# cnc_1_0_0.net
KiCad netlist of a schematic drawn in EAGLE
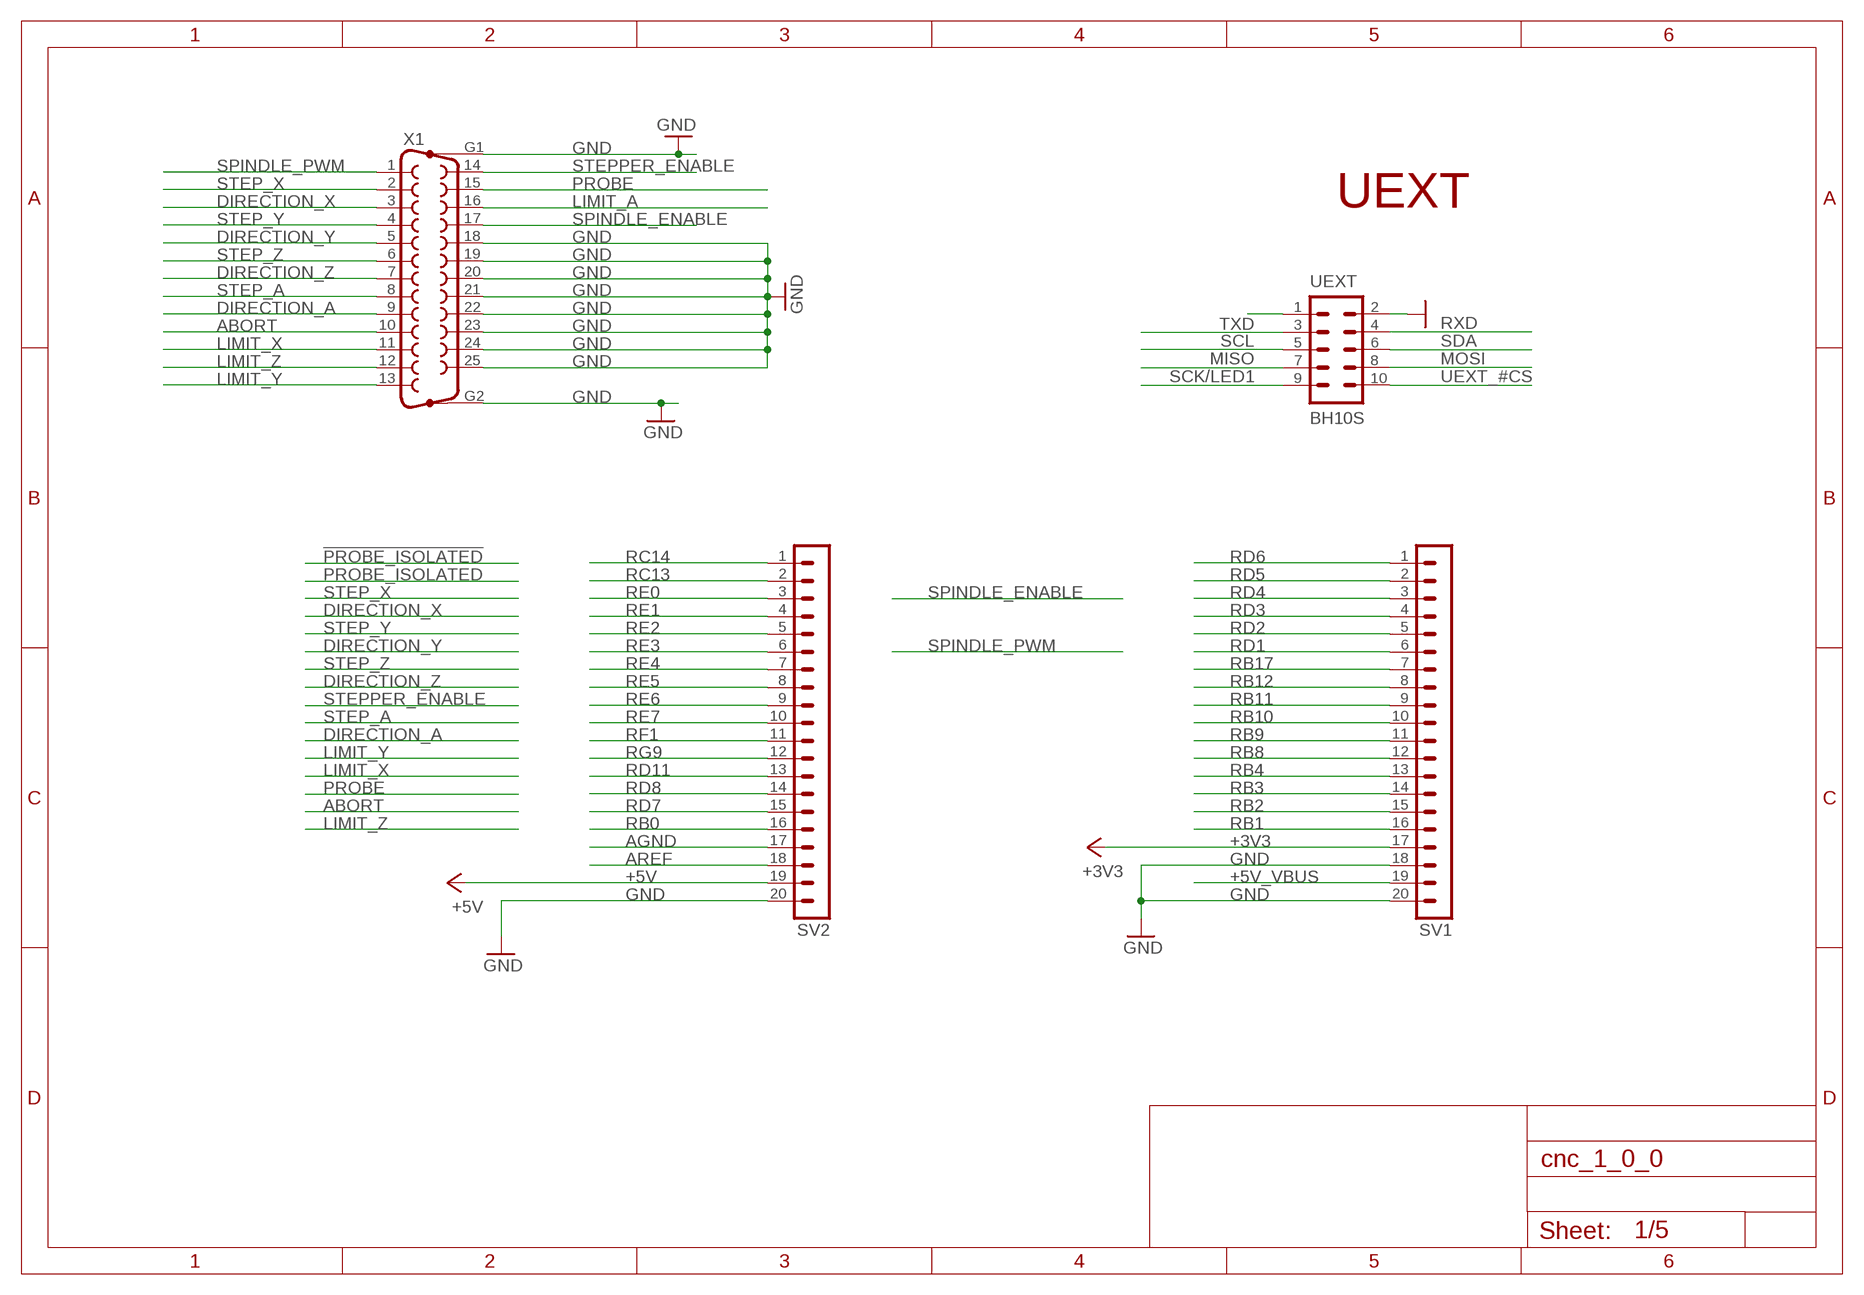
[diagram p0: schematic, sheet 1]
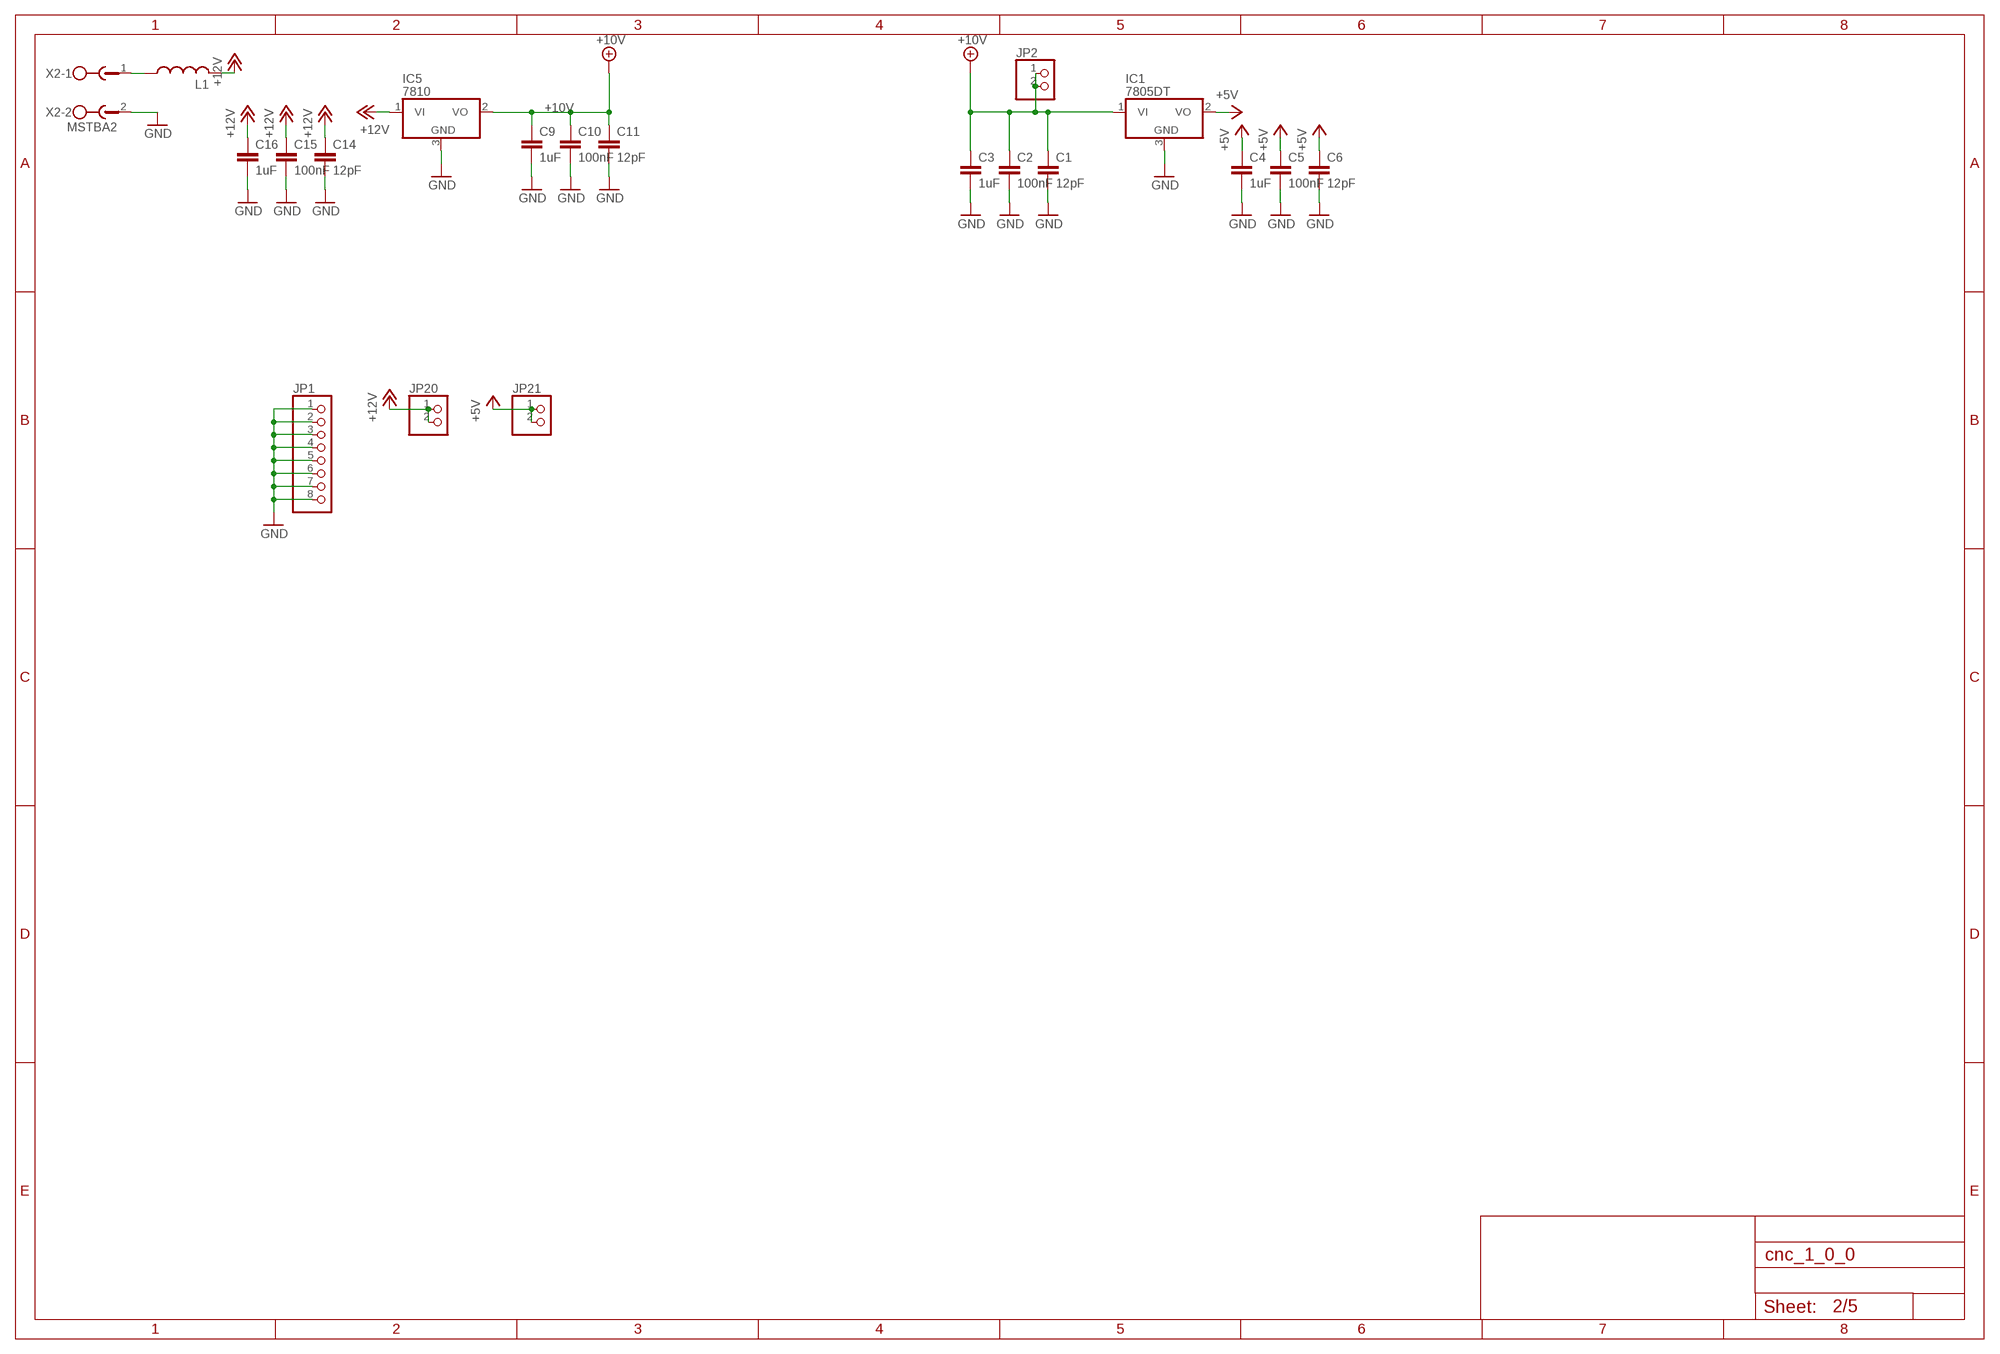
[diagram p1: schematic, sheet 2]
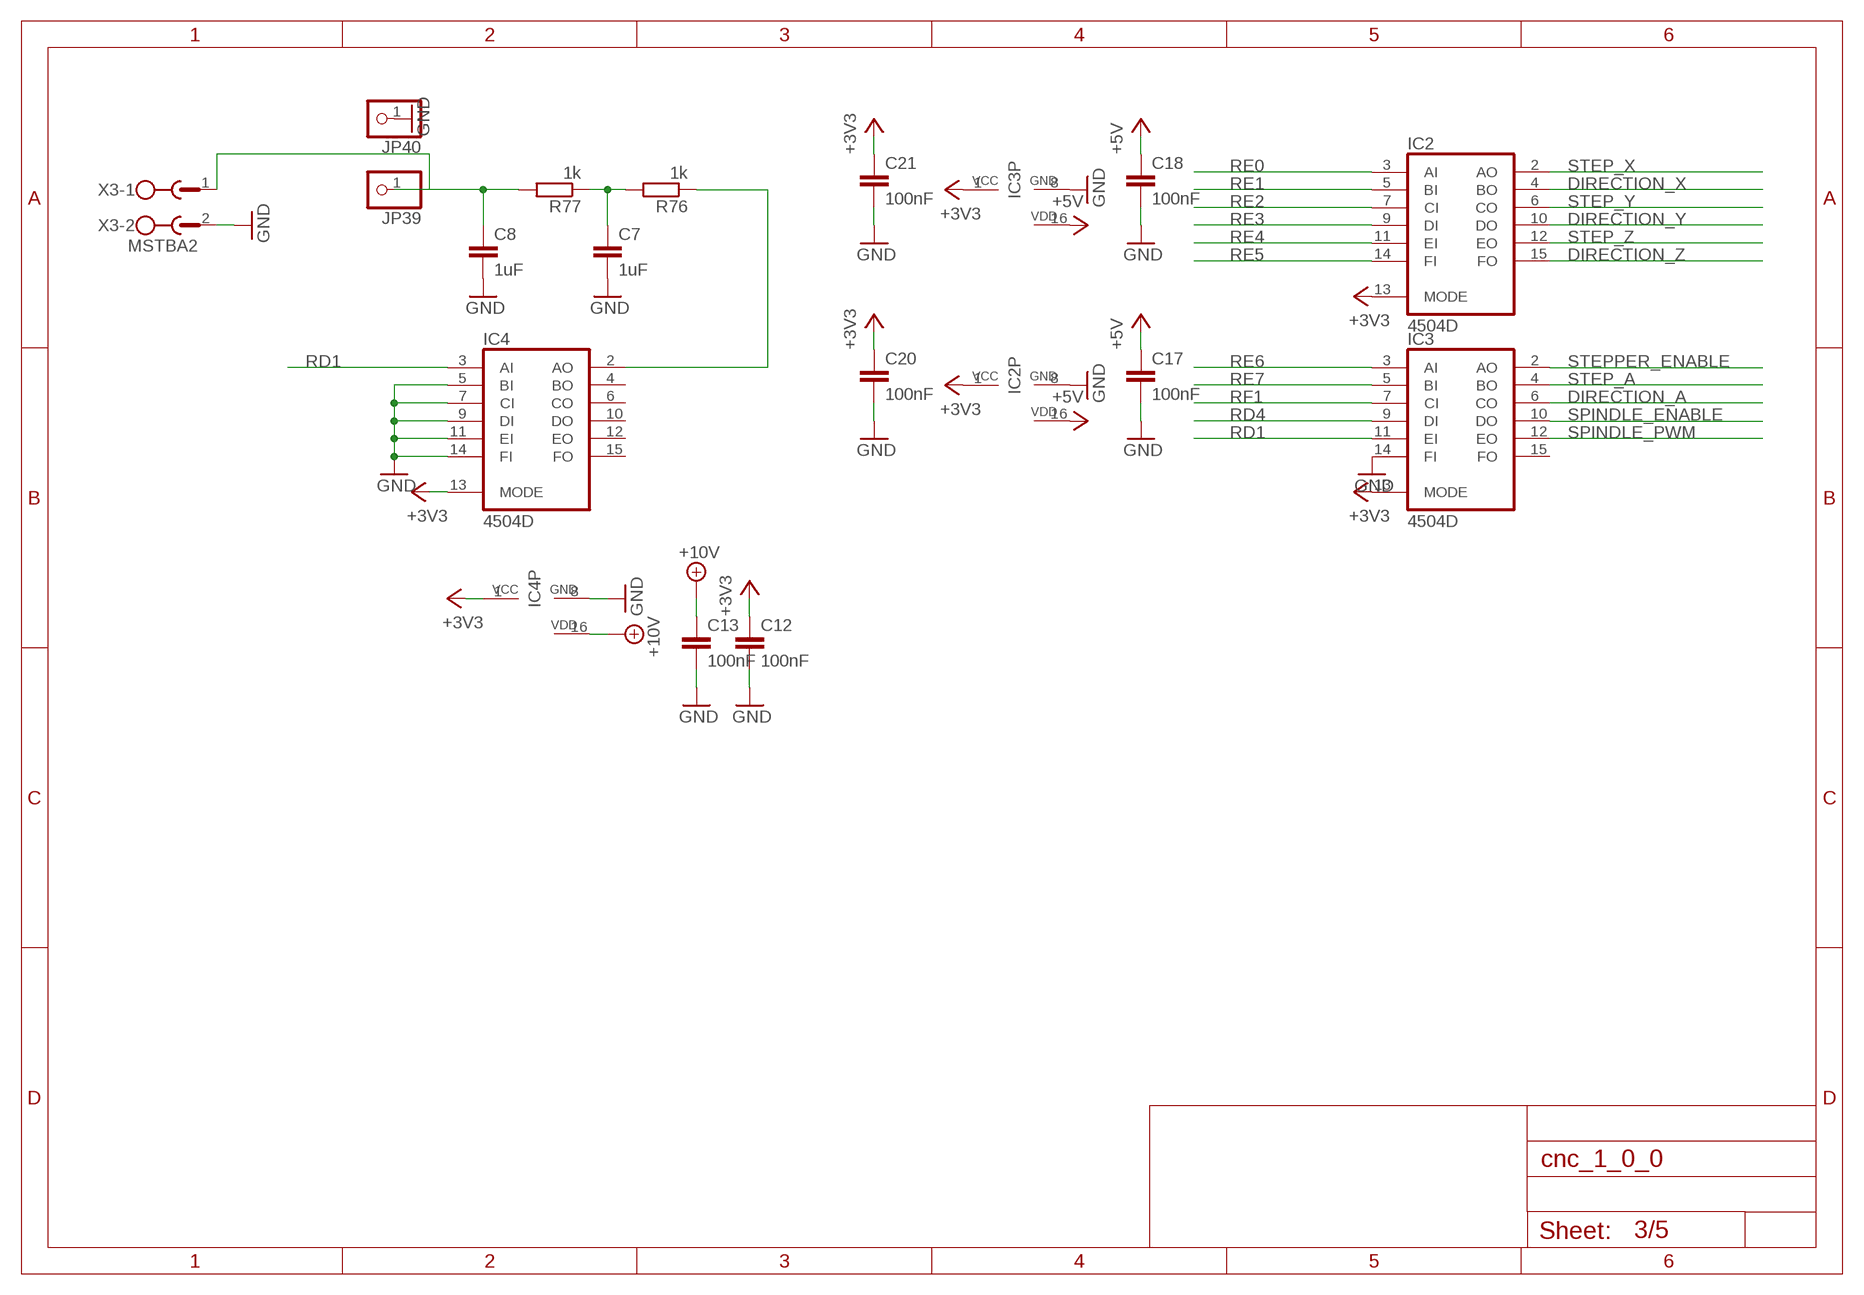
[diagram p2: schematic, sheet 3]
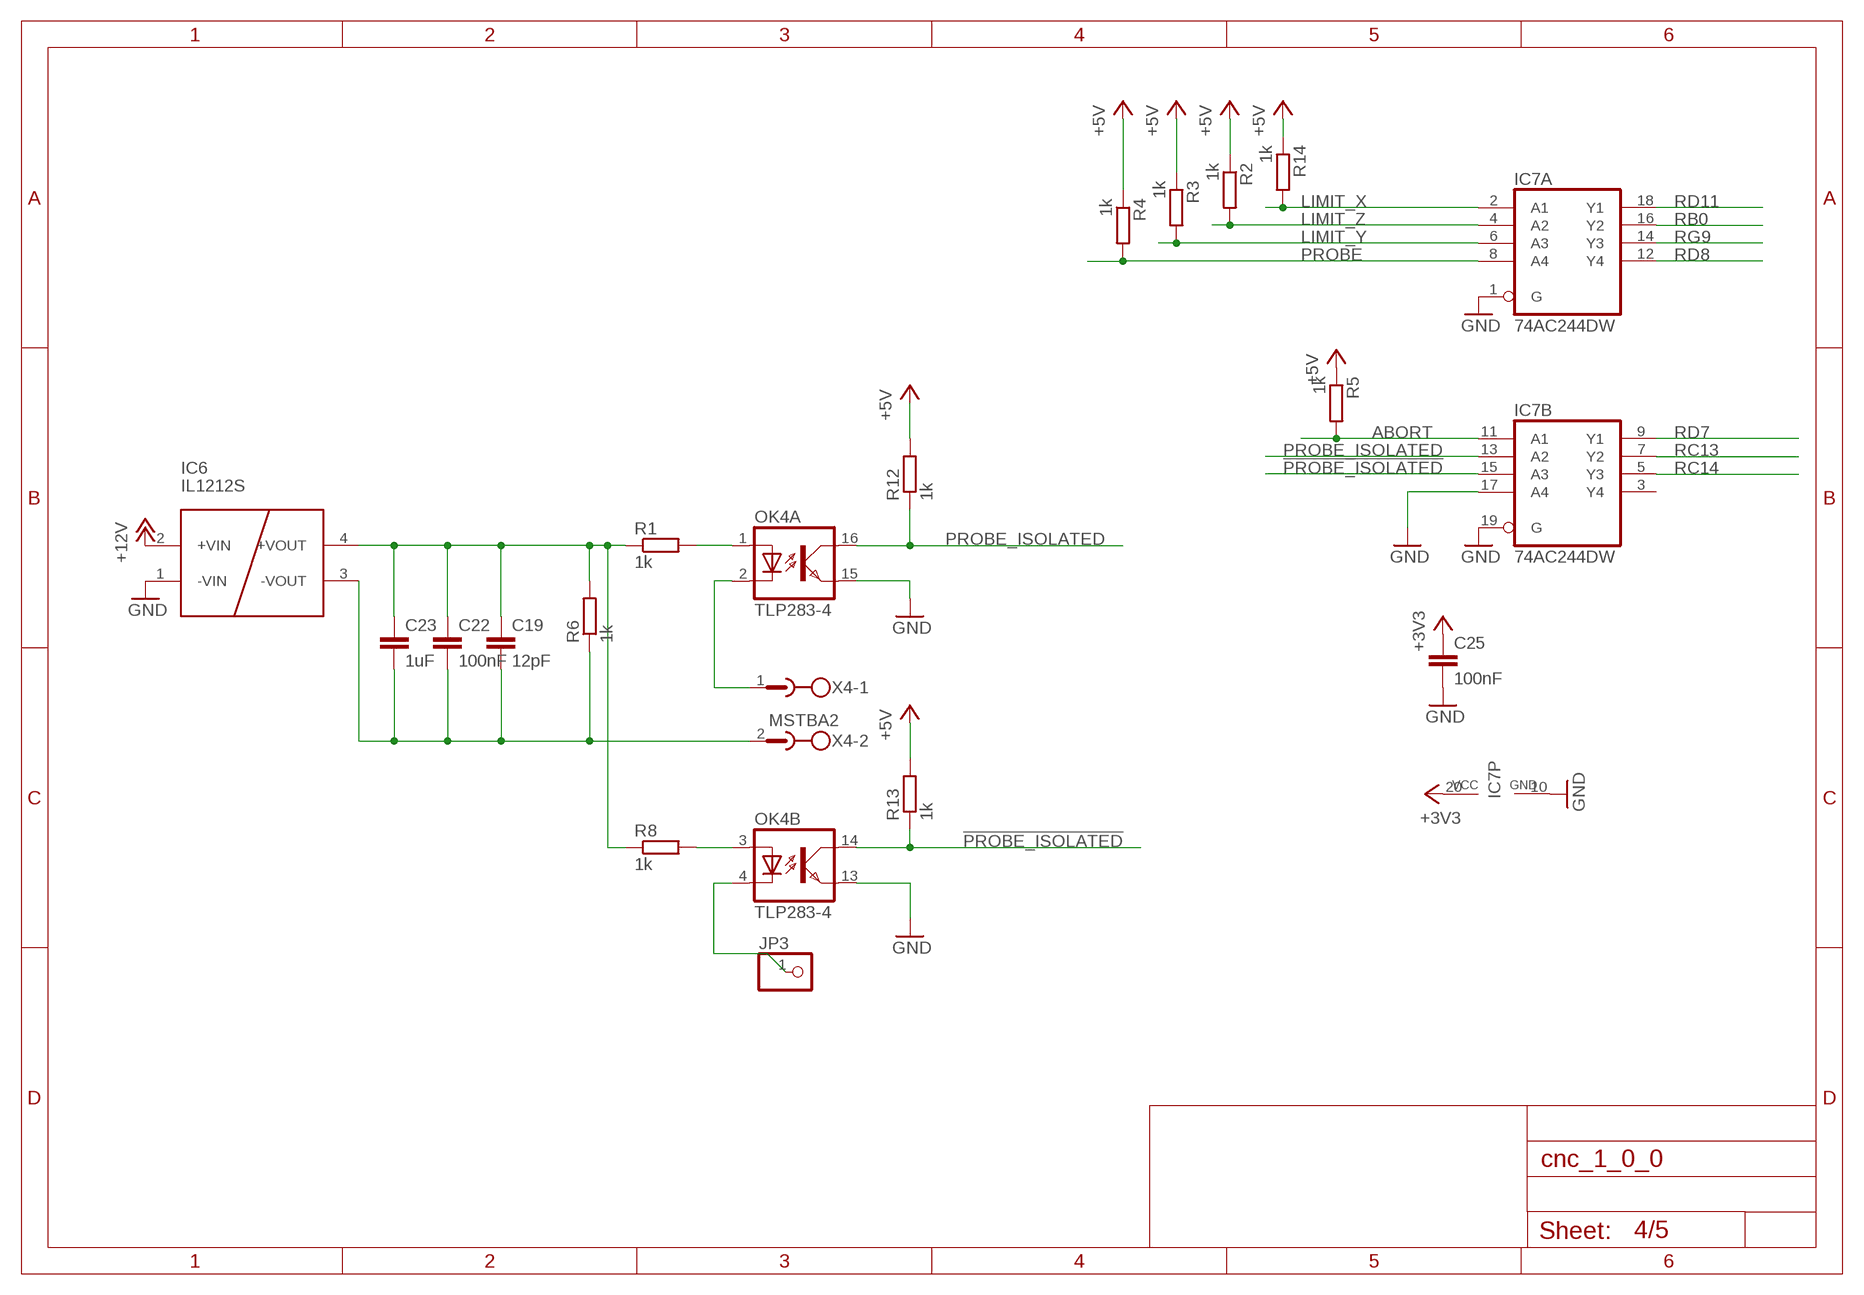
[diagram p3: schematic, sheet 4]
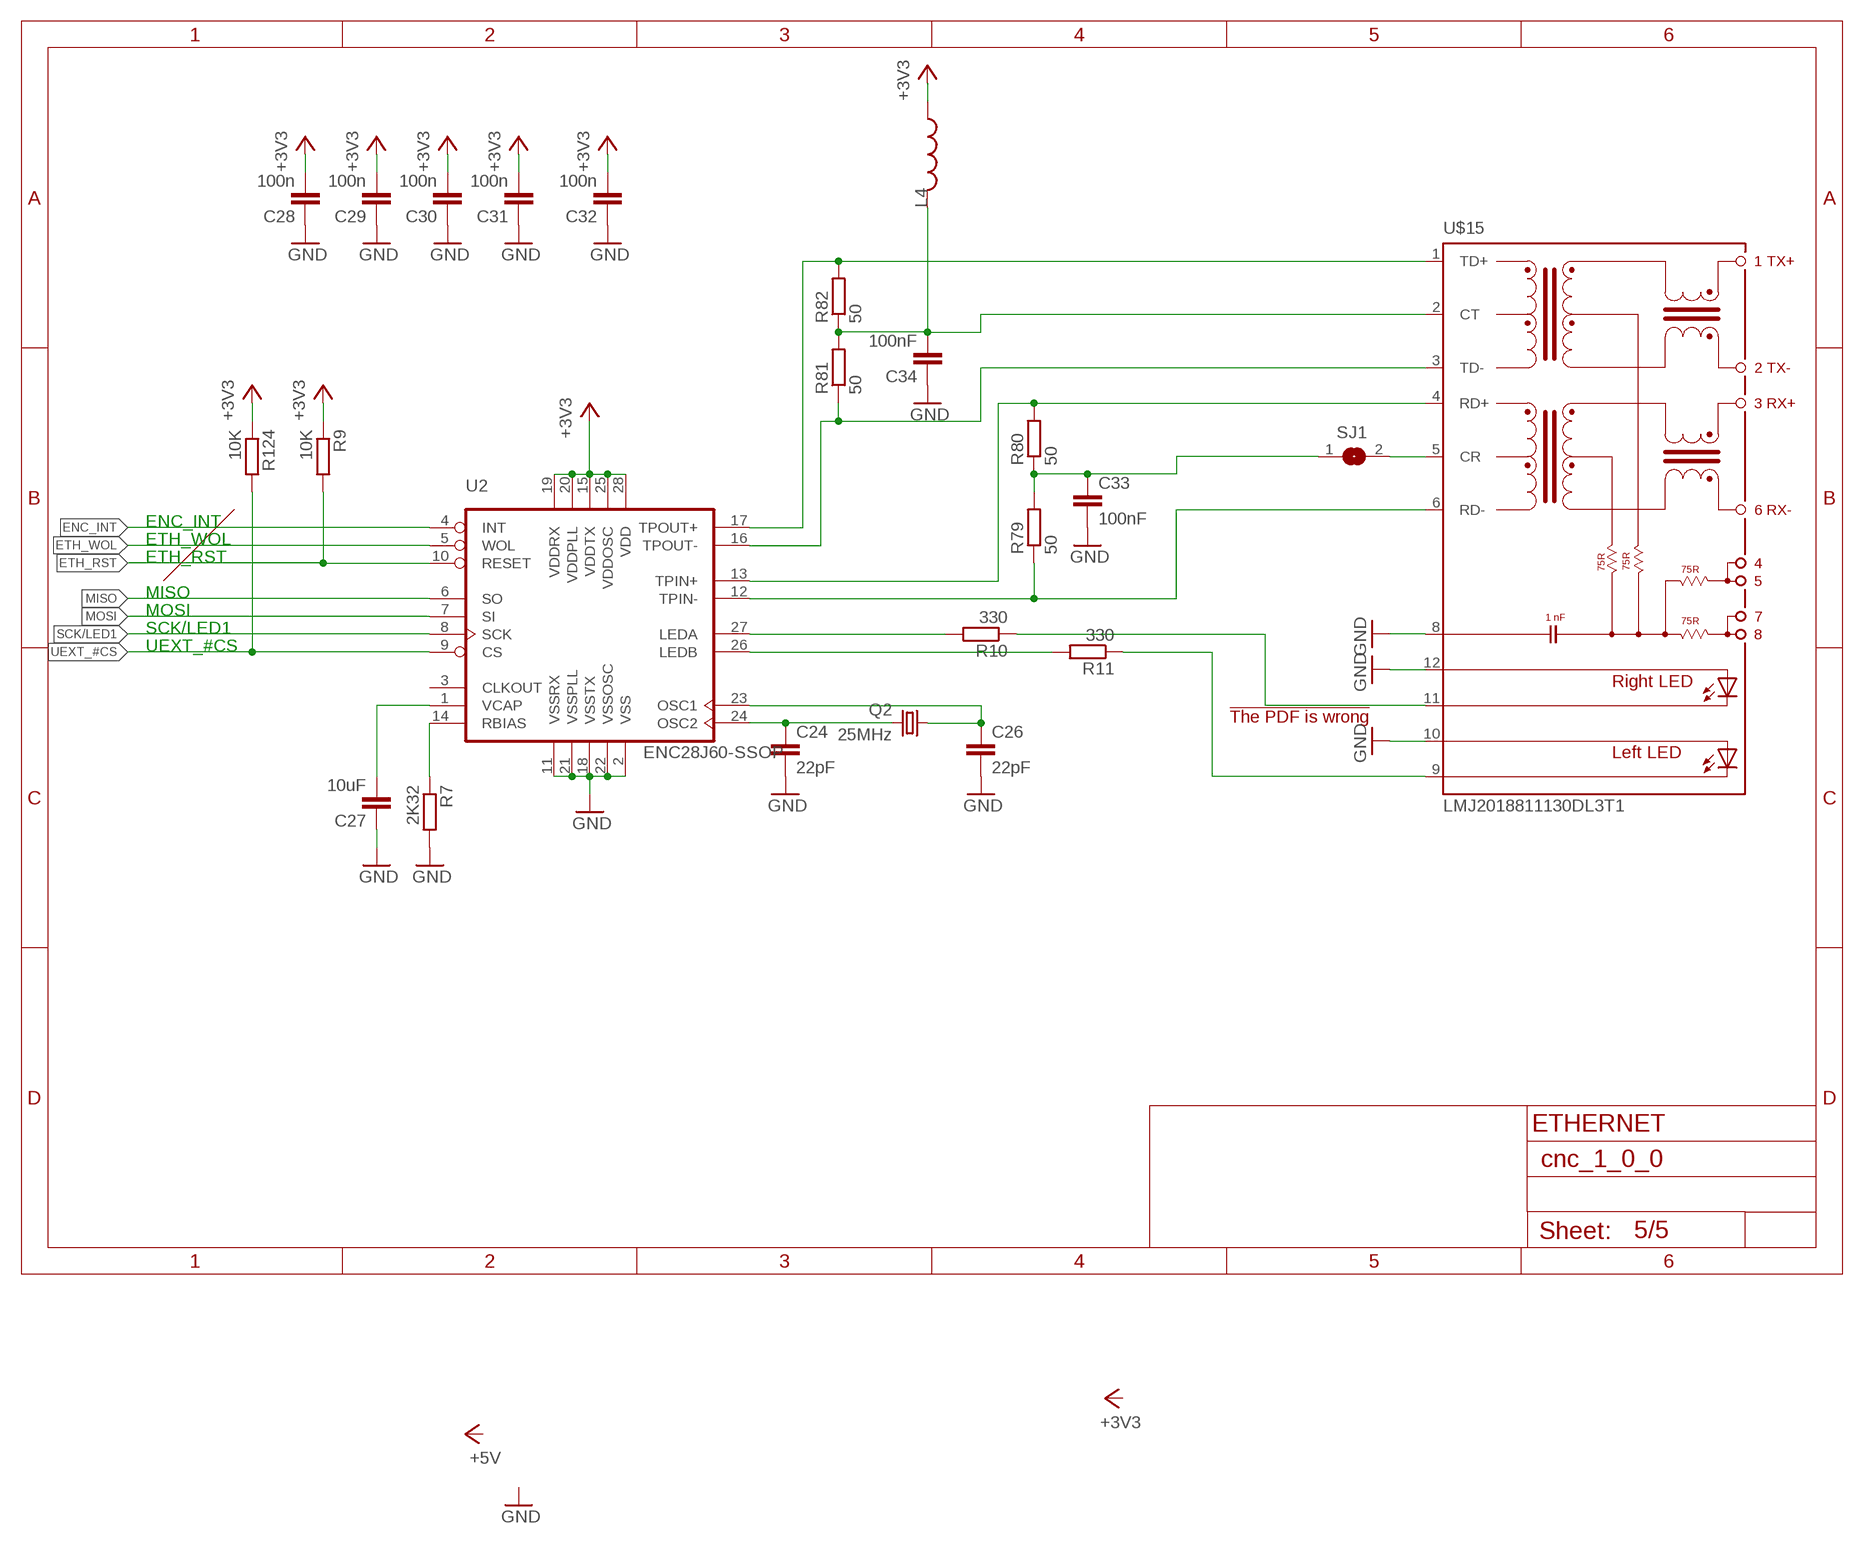
[diagram p4: schematic, sheet 5]

(export (version "E")
  (design (tool "Eeschema 10.0.6"))
  (components
    (comp (ref "C7")
      (value "1uF")
      (footprint "eagle-import:C0805K")
      (libsource (lib "eagle-import") (part "C-EUC0805K"))
    )
    (comp (ref "C8")
      (value "1uF")
      (footprint "eagle-import:C0805K")
      (libsource (lib "eagle-import") (part "C-EUC0805K"))
    )
    (comp (ref "C12")
      (value "100nF")
      (footprint "eagle-import:C0805K")
      (libsource (lib "eagle-import") (part "C-EUC0805K"))
    )
    (comp (ref "C13")
      (value "100nF")
      (footprint "eagle-import:C0805K")
      (libsource (lib "eagle-import") (part "C-EUC0805K"))
    )
    (comp (ref "C17")
      (value "100nF")
      (footprint "eagle-import:C0805K")
      (libsource (lib "eagle-import") (part "C-EUC0805K"))
    )
    (comp (ref "C18")
      (value "100nF")
      (footprint "eagle-import:C0805K")
      (libsource (lib "eagle-import") (part "C-EUC0805K"))
    )
    (comp (ref "C20")
      (value "100nF")
      (footprint "eagle-import:C0805K")
      (libsource (lib "eagle-import") (part "C-EUC0805K"))
    )
    (comp (ref "C21")
      (value "100nF")
      (footprint "eagle-import:C0805K")
      (libsource (lib "eagle-import") (part "C-EUC0805K"))
    )
    (comp (ref "IC2")
      (value "4504D")
      (footprint "eagle-import:SO16")
      (libsource (lib "eagle-import") (part "4504D"))
    )
    (comp (ref "IC3")
      (value "4504D")
      (footprint "eagle-import:SO16")
      (libsource (lib "eagle-import") (part "4504D"))
    )
    (comp (ref "IC4")
      (value "4504D")
      (footprint "eagle-import:SO16")
      (libsource (lib "eagle-import") (part "4504D"))
    )
    (comp (ref "JP39")
      (value "PINHD-1X1")
      (footprint "eagle-import:1X01")
      (libsource (lib "eagle-import") (part "PINHD-1X1"))
    )
    (comp (ref "JP40")
      (value "PINHD-1X1")
      (footprint "eagle-import:1X01")
      (libsource (lib "eagle-import") (part "PINHD-1X1"))
    )
    (comp (ref "R76")
      (value "1k")
      (footprint "eagle-import:R0805")
      (libsource (lib "eagle-import") (part "R-EU_R0805"))
    )
    (comp (ref "R77")
      (value "1k")
      (footprint "eagle-import:R0805")
      (libsource (lib "eagle-import") (part "R-EU_R0805"))
    )
    (comp (ref "X3")
      (value "MSTBA2")
      (footprint "eagle-import:MSTBA2")
      (fields
        (field (name "MF") "FARNELL")
        (field (name "MPN") "1757242")
        (field (name "MF_1") "FARNELL")
        (field (name "MPN_1") "1757242")
        (field (name "OC_FARNELL") "3705171")
        (field (name "OC_NEWARK") "71C4161")
      )
      (libsource (lib "eagle-import") (part "MSTBA2"))
    )
    (comp (ref "C24")
      (value "22pF")
      (footprint "eagle-import:C0603")
      (libsource (lib "eagle-import") (part "C-EUC0603"))
    )
    (comp (ref "C26")
      (value "22pF")
      (footprint "eagle-import:C0603")
      (libsource (lib "eagle-import") (part "C-EUC0603"))
    )
    (comp (ref "C27")
      (value "10uF")
      (footprint "eagle-import:C0805K")
      (libsource (lib "eagle-import") (part "C-EUC0805K"))
    )
    (comp (ref "C28")
      (value "100n")
      (footprint "eagle-import:C0603")
      (libsource (lib "eagle-import") (part "C-EUC0603"))
    )
    (comp (ref "C29")
      (value "100n")
      (footprint "eagle-import:C0603")
      (libsource (lib "eagle-import") (part "C-EUC0603"))
    )
    (comp (ref "C30")
      (value "100n")
      (footprint "eagle-import:C0603")
      (libsource (lib "eagle-import") (part "C-EUC0603"))
    )
    (comp (ref "C31")
      (value "100n")
      (footprint "eagle-import:C0603")
      (libsource (lib "eagle-import") (part "C-EUC0603"))
    )
    (comp (ref "C32")
      (value "100n")
      (footprint "eagle-import:C0603")
      (libsource (lib "eagle-import") (part "C-EUC0603"))
    )
    (comp (ref "C33")
      (value "100nF")
      (footprint "eagle-import:C0603")
      (libsource (lib "eagle-import") (part "C-EUC0603"))
    )
    (comp (ref "C34")
      (value "100nF")
      (footprint "eagle-import:C0603")
      (libsource (lib "eagle-import") (part "C-EUC0603"))
    )
    (comp (ref "L4")
      (value "INDUCTOR0603")
      (footprint "eagle-import:0603")
      (libsource (lib "eagle-import") (part "INDUCTOR0603"))
    )
    (comp (ref "Q2")
      (value "25MHz")
      (footprint "eagle-import:CRYSTAL-SMD-5X3")
      (libsource (lib "eagle-import") (part "CRYSTAL5X3"))
    )
    (comp (ref "R7")
      (value "2K32")
      (footprint "eagle-import:R0805")
      (libsource (lib "eagle-import") (part "R-EU_R0805"))
    )
    (comp (ref "R9")
      (value "10K")
      (footprint "eagle-import:R0805")
      (libsource (lib "eagle-import") (part "R-EU_R0805"))
    )
    (comp (ref "R10")
      (value "330")
      (footprint "eagle-import:R0805")
      (libsource (lib "eagle-import") (part "R-EU_R0805"))
    )
    (comp (ref "R11")
      (value "330")
      (footprint "eagle-import:R0805")
      (libsource (lib "eagle-import") (part "R-EU_R0805"))
    )
    (comp (ref "R79")
      (value "50")
      (footprint "eagle-import:R0603")
      (libsource (lib "eagle-import") (part "R-EU_R0603"))
    )
    (comp (ref "R80")
      (value "50")
      (footprint "eagle-import:R0603")
      (libsource (lib "eagle-import") (part "R-EU_R0603"))
    )
    (comp (ref "R81")
      (value "50")
      (footprint "eagle-import:R0603")
      (libsource (lib "eagle-import") (part "R-EU_R0603"))
    )
    (comp (ref "R82")
      (value "50")
      (footprint "eagle-import:R0603")
      (libsource (lib "eagle-import") (part "R-EU_R0603"))
    )
    (comp (ref "R124")
      (value "10K")
      (footprint "eagle-import:R0805")
      (libsource (lib "eagle-import") (part "R-EU_R0805"))
    )
    (comp (ref "SJ1") (value "SJ") (footprint "eagle-import:SJ") (libsource (lib "eagle-import") (part "SJ")))
    (comp (ref "U$15")
      (value "LMJ2018811130DL3T1")
      (footprint "eagle-import:AMPHENOL-LMJ2018814100DL2T1B_RJ45")
      (libsource (lib "eagle-import") (part "AMPHENOL-LMJ2018814100DL2T1B_LMJ2018814100DL"))
    )
    (comp (ref "U2")
      (value "ENC28J60-SSOP")
      (footprint "eagle-import:SSOP28")
      (libsource (lib "eagle-import") (part "ENC28J60-SSOP"))
    )
    (comp (ref "SV1")
      (value "MA20-1")
      (footprint "eagle-import:MA20-1")
      (libsource (lib "eagle-import") (part "MA20-1"))
    )
    (comp (ref "SV2")
      (value "MA20-1")
      (footprint "eagle-import:MA20-1")
      (libsource (lib "eagle-import") (part "MA20-1"))
    )
    (comp (ref "UEXT")
      (value "BH10S")
      (footprint "eagle-import:ML10-MALE")
      (libsource (lib "eagle-import") (part "ML10"))
    )
    (comp (ref "X1")
      (value "F25HP")
      (footprint "eagle-import:F25HP")
      (libsource (lib "eagle-import") (part "F25HP"))
    )
    (comp (ref "C19")
      (value "12pF")
      (footprint "eagle-import:C0805K")
      (libsource (lib "eagle-import") (part "C-EUC0805K"))
    )
    (comp (ref "C22")
      (value "100nF")
      (footprint "eagle-import:C0805K")
      (libsource (lib "eagle-import") (part "C-EUC0805K"))
    )
    (comp (ref "C23")
      (value "1uF")
      (footprint "eagle-import:C0805K")
      (libsource (lib "eagle-import") (part "C-EUC0805K"))
    )
    (comp (ref "C25")
      (value "100nF")
      (footprint "eagle-import:C0805K")
      (libsource (lib "eagle-import") (part "C-EUC0805K"))
    )
    (comp (ref "IC6")
      (value "IL1212S")
      (footprint "eagle-import:SIL4")
      (libsource (lib "eagle-import") (part "IL0512S"))
    )
    (comp (ref "IC7")
      (value "74AC244DW")
      (footprint "eagle-import:SO20W")
      (libsource (lib "eagle-import") (part "74244DWAC"))
    )
    (comp (ref "JP3")
      (value "PINHD-1X1")
      (footprint "eagle-import:1X01")
      (libsource (lib "eagle-import") (part "PINHD-1X1"))
    )
    (comp (ref "OK4")
      (value "TLP283-4")
      (footprint "eagle-import:MINI-FLAT-16")
      (libsource (lib "eagle-import") (part "TLP283-4"))
    )
    (comp (ref "R1")
      (value "1k")
      (footprint "eagle-import:R0805")
      (libsource (lib "eagle-import") (part "R-EU_R0805"))
    )
    (comp (ref "R2")
      (value "1k")
      (footprint "eagle-import:R0805")
      (libsource (lib "eagle-import") (part "R-EU_R0805"))
    )
    (comp (ref "R3")
      (value "1k")
      (footprint "eagle-import:R0805")
      (libsource (lib "eagle-import") (part "R-EU_R0805"))
    )
    (comp (ref "R4")
      (value "1k")
      (footprint "eagle-import:R0805")
      (libsource (lib "eagle-import") (part "R-EU_R0805"))
    )
    (comp (ref "R5")
      (value "1k")
      (footprint "eagle-import:R0805")
      (libsource (lib "eagle-import") (part "R-EU_R0805"))
    )
    (comp (ref "R6")
      (value "1k")
      (footprint "eagle-import:R0805")
      (libsource (lib "eagle-import") (part "R-EU_R0805"))
    )
    (comp (ref "R8")
      (value "1k")
      (footprint "eagle-import:R0805")
      (libsource (lib "eagle-import") (part "R-EU_R0805"))
    )
    (comp (ref "R12")
      (value "1k")
      (footprint "eagle-import:R0805")
      (libsource (lib "eagle-import") (part "R-EU_R0805"))
    )
    (comp (ref "R13")
      (value "1k")
      (footprint "eagle-import:R0805")
      (libsource (lib "eagle-import") (part "R-EU_R0805"))
    )
    (comp (ref "R14")
      (value "1k")
      (footprint "eagle-import:R0805")
      (libsource (lib "eagle-import") (part "R-EU_R0805"))
    )
    (comp (ref "X4")
      (value "MSTBA2")
      (footprint "eagle-import:MSTBA2")
      (fields
        (field (name "MF") "FARNELL")
        (field (name "MPN") "1757242")
        (field (name "MF_1") "FARNELL")
        (field (name "MPN_1") "1757242")
        (field (name "OC_FARNELL") "3705171")
        (field (name "OC_NEWARK") "71C4161")
      )
      (libsource (lib "eagle-import") (part "MSTBA2"))
    )
    (comp (ref "C1")
      (value "12pF")
      (footprint "eagle-import:C0805K")
      (libsource (lib "eagle-import") (part "C-EUC0805K"))
    )
    (comp (ref "C2")
      (value "100nF")
      (footprint "eagle-import:C0805K")
      (libsource (lib "eagle-import") (part "C-EUC0805K"))
    )
    (comp (ref "C3")
      (value "1uF")
      (footprint "eagle-import:C0805K")
      (libsource (lib "eagle-import") (part "C-EUC0805K"))
    )
    (comp (ref "C4")
      (value "1uF")
      (footprint "eagle-import:C0805K")
      (libsource (lib "eagle-import") (part "C-EUC0805K"))
    )
    (comp (ref "C5")
      (value "100nF")
      (footprint "eagle-import:C0805K")
      (libsource (lib "eagle-import") (part "C-EUC0805K"))
    )
    (comp (ref "C6")
      (value "12pF")
      (footprint "eagle-import:C0805K")
      (libsource (lib "eagle-import") (part "C-EUC0805K"))
    )
    (comp (ref "C9")
      (value "1uF")
      (footprint "eagle-import:C0805K")
      (libsource (lib "eagle-import") (part "C-EUC0805K"))
    )
    (comp (ref "C10")
      (value "100nF")
      (footprint "eagle-import:C0805K")
      (libsource (lib "eagle-import") (part "C-EUC0805K"))
    )
    (comp (ref "C11")
      (value "12pF")
      (footprint "eagle-import:C0805K")
      (libsource (lib "eagle-import") (part "C-EUC0805K"))
    )
    (comp (ref "C14")
      (value "12pF")
      (footprint "eagle-import:C0805K")
      (libsource (lib "eagle-import") (part "C-EUC0805K"))
    )
    (comp (ref "C15")
      (value "100nF")
      (footprint "eagle-import:C0805K")
      (libsource (lib "eagle-import") (part "C-EUC0805K"))
    )
    (comp (ref "C16")
      (value "1uF")
      (footprint "eagle-import:C0805K")
      (libsource (lib "eagle-import") (part "C-EUC0805K"))
    )
    (comp (ref "IC1")
      (value "7805DT")
      (footprint "eagle-import:TO252")
      (libsource (lib "eagle-import") (part "78DT05"))
    )
    (comp (ref "IC5")
      (value "7810")
      (footprint "eagle-import:TO252")
      (libsource (lib "eagle-import") (part "78DT05"))
    )
    (comp (ref "JP1")
      (value "PINHD-1X8")
      (footprint "eagle-import:1X08")
      (libsource (lib "eagle-import") (part "PINHD-1X8"))
    )
    (comp (ref "JP2")
      (value "PINHD-1X2")
      (footprint "eagle-import:1X02")
      (libsource (lib "eagle-import") (part "PINHD-1X2"))
    )
    (comp (ref "JP20")
      (value "PINHD-1X2")
      (footprint "eagle-import:1X02")
      (libsource (lib "eagle-import") (part "PINHD-1X2"))
    )
    (comp (ref "JP21")
      (value "PINHD-1X2")
      (footprint "eagle-import:1X02")
      (libsource (lib "eagle-import") (part "PINHD-1X2"))
    )
    (comp (ref "L1")
      (value "L-USL1812")
      (footprint "eagle-import:L1812")
      (libsource (lib "eagle-import") (part "L-USL1812"))
    )
    (comp (ref "X2")
      (value "MSTBA2")
      (footprint "eagle-import:MSTBA2")
      (fields (field (name "MF") "FARNELL") (field (name "MPN") "1757242"))
      (libsource (lib "eagle-import") (part "MSTBA2"))
    )
  )
  (nets
    (net (code "1") (name "+3V3") (class "Default")
      (node (ref "C12") (pin "1") (pinfunction "1_1") (pintype "passive"))
      (node (ref "C20") (pin "1") (pinfunction "1_1") (pintype "passive"))
      (node (ref "C21") (pin "1") (pinfunction "1_1") (pintype "passive"))
      (node (ref "C25") (pin "1") (pinfunction "1_1") (pintype "passive"))
      (node (ref "C28") (pin "2") (pinfunction "2_2") (pintype "passive"))
      (node (ref "C29") (pin "2") (pinfunction "2_2") (pintype "passive"))
      (node (ref "C30") (pin "2") (pinfunction "2_2") (pintype "passive"))
      (node (ref "C31") (pin "2") (pinfunction "2_2") (pintype "passive"))
      (node (ref "C32") (pin "2") (pinfunction "2_2") (pintype "passive"))
      (node (ref "IC2") (pin "1") (pinfunction "VCC_1") (pintype "power_in"))
      (node (ref "IC2") (pin "13") (pinfunction "MODE_13") (pintype "input"))
      (node (ref "IC3") (pin "1") (pinfunction "VCC_1") (pintype "power_in"))
      (node (ref "IC3") (pin "13") (pinfunction "MODE_13") (pintype "input"))
      (node (ref "IC4") (pin "1") (pinfunction "VCC_1") (pintype "power_in"))
      (node (ref "IC4") (pin "13") (pinfunction "MODE_13") (pintype "input"))
      (node (ref "IC7") (pin "20") (pinfunction "VCC_20") (pintype "power_in"))
      (node (ref "L4") (pin "1") (pinfunction "1_1") (pintype "passive"))
      (node (ref "R124") (pin "1") (pinfunction "1_1") (pintype "passive"))
      (node (ref "R9") (pin "1") (pinfunction "1_1") (pintype "passive"))
      (node (ref "SV1") (pin "17") (pinfunction "17_17") (pintype "passive"))
      (node (ref "U2") (pin "15") (pinfunction "VDDTX_15") (pintype "power_in"))
      (node (ref "U2") (pin "19") (pinfunction "VDDRX_19") (pintype "power_in"))
      (node (ref "U2") (pin "20") (pinfunction "VDDPLL_20") (pintype "power_in"))
      (node (ref "U2") (pin "25") (pinfunction "VDDOSC_25") (pintype "power_in"))
      (node (ref "U2") (pin "28") (pinfunction "VDD_28") (pintype "power_in"))
    )
    (net (code "2") (name "+5V") (class "Default")
      (node (ref "C17") (pin "1") (pinfunction "1_1") (pintype "passive"))
      (node (ref "C18") (pin "1") (pinfunction "1_1") (pintype "passive"))
      (node (ref "C4") (pin "1") (pinfunction "1_1") (pintype "passive"))
      (node (ref "C5") (pin "1") (pinfunction "1_1") (pintype "passive"))
      (node (ref "C6") (pin "1") (pinfunction "1_1") (pintype "passive"))
      (node (ref "IC1") (pin "2") (pinfunction "VO_2") (pintype "passive"))
      (node (ref "IC2") (pin "16") (pinfunction "VDD_16") (pintype "power_in"))
      (node (ref "IC3") (pin "16") (pinfunction "VDD_16") (pintype "power_in"))
      (node (ref "JP21") (pin "1") (pinfunction "1_1") (pintype "passive"))
      (node (ref "JP21") (pin "2") (pinfunction "2_2") (pintype "passive"))
      (node (ref "R12") (pin "2") (pinfunction "2_2") (pintype "passive"))
      (node (ref "R13") (pin "2") (pinfunction "2_2") (pintype "passive"))
      (node (ref "R14") (pin "1") (pinfunction "1_1") (pintype "passive"))
      (node (ref "R2") (pin "1") (pinfunction "1_1") (pintype "passive"))
      (node (ref "R3") (pin "1") (pinfunction "1_1") (pintype "passive"))
      (node (ref "R4") (pin "1") (pinfunction "1_1") (pintype "passive"))
      (node (ref "R5") (pin "1") (pinfunction "1_1") (pintype "passive"))
      (node (ref "SV2") (pin "19") (pinfunction "19_19") (pintype "passive"))
    )
    (net (code "3") (name "+5V_VBUS") (class "Default")
      (node (ref "SV1") (pin "19") (pinfunction "19_19") (pintype "passive"))
    )
    (net (code "4") (name "+10V") (class "Default")
      (node (ref "C1") (pin "1") (pinfunction "1_1") (pintype "passive"))
      (node (ref "C10") (pin "1") (pinfunction "1_1") (pintype "passive"))
      (node (ref "C11") (pin "1") (pinfunction "1_1") (pintype "passive"))
      (node (ref "C13") (pin "1") (pinfunction "1_1") (pintype "passive"))
      (node (ref "C2") (pin "1") (pinfunction "1_1") (pintype "passive"))
      (node (ref "C3") (pin "1") (pinfunction "1_1") (pintype "passive"))
      (node (ref "C9") (pin "1") (pinfunction "1_1") (pintype "passive"))
      (node (ref "IC1") (pin "1") (pinfunction "VI_1") (pintype "input"))
      (node (ref "IC4") (pin "16") (pinfunction "VDD_16") (pintype "power_in"))
      (node (ref "IC5") (pin "2") (pinfunction "VO_2") (pintype "passive"))
      (node (ref "JP2") (pin "1") (pinfunction "1_1") (pintype "passive"))
      (node (ref "JP2") (pin "2") (pinfunction "2_2") (pintype "passive"))
    )
    (net (code "5") (name "+12V") (class "Default")
      (node (ref "C14") (pin "1") (pinfunction "1_1") (pintype "passive"))
      (node (ref "C15") (pin "1") (pinfunction "1_1") (pintype "passive"))
      (node (ref "C16") (pin "1") (pinfunction "1_1") (pintype "passive"))
      (node (ref "IC5") (pin "1") (pinfunction "VI_1") (pintype "input"))
      (node (ref "IC6") (pin "2") (pinfunction "+VIN_2") (pintype "bidirectional"))
      (node (ref "JP20") (pin "1") (pinfunction "1_1") (pintype "passive"))
      (node (ref "JP20") (pin "2") (pinfunction "2_2") (pintype "passive"))
      (node (ref "L1") (pin "2") (pinfunction "2_2") (pintype "passive"))
    )
    (net (code "6") (name "ABORT") (class "Default")
      (node (ref "IC7") (pin "11") (pinfunction "A1_11") (pintype "input"))
      (node (ref "R5") (pin "2") (pinfunction "2_2") (pintype "passive"))
      (node (ref "X1") (pin "10") (pinfunction "10_10") (pintype "passive"))
    )
    (net (code "7") (name "AGND") (class "Default")
      (node (ref "SV2") (pin "17") (pinfunction "17_17") (pintype "passive"))
    )
    (net (code "8") (name "AREF") (class "Default")
      (node (ref "SV2") (pin "18") (pinfunction "18_18") (pintype "passive"))
    )
    (net (code "9") (name "DIRECTION_A") (class "Default")
      (node (ref "IC3") (pin "6") (pinfunction "CO_6") (pintype "output"))
      (node (ref "X1") (pin "9") (pinfunction "9_9") (pintype "passive"))
    )
    (net (code "10") (name "DIRECTION_X") (class "Default")
      (node (ref "IC2") (pin "4") (pinfunction "BO_4") (pintype "output"))
      (node (ref "X1") (pin "3") (pinfunction "3_3") (pintype "passive"))
    )
    (net (code "11") (name "DIRECTION_Y") (class "Default")
      (node (ref "IC2") (pin "10") (pinfunction "DO_10") (pintype "output"))
      (node (ref "X1") (pin "5") (pinfunction "5_5") (pintype "passive"))
    )
    (net (code "12") (name "DIRECTION_Z") (class "Default")
      (node (ref "IC2") (pin "15") (pinfunction "FO_15") (pintype "output"))
      (node (ref "X1") (pin "7") (pinfunction "7_7") (pintype "passive"))
    )
    (net (code "13") (name "ENC_INT") (class "Default")
      (node (ref "U2") (pin "4") (pinfunction "INT_4") (pintype "output"))
    )
    (net (code "14") (name "ETH_RST") (class "Default")
      (node (ref "R9") (pin "2") (pinfunction "2_2") (pintype "passive"))
      (node (ref "U2") (pin "10") (pinfunction "RESET_10") (pintype "input"))
    )
    (net (code "15") (name "ETH_WOL") (class "Default")
      (node (ref "U2") (pin "5") (pinfunction "WOL_5") (pintype "output"))
    )
    (net (code "16") (name "GND") (class "Default")
      (node (ref "C1") (pin "2") (pinfunction "2_2") (pintype "passive"))
      (node (ref "C10") (pin "2") (pinfunction "2_2") (pintype "passive"))
      (node (ref "C11") (pin "2") (pinfunction "2_2") (pintype "passive"))
      (node (ref "C12") (pin "2") (pinfunction "2_2") (pintype "passive"))
      (node (ref "C13") (pin "2") (pinfunction "2_2") (pintype "passive"))
      (node (ref "C14") (pin "2") (pinfunction "2_2") (pintype "passive"))
      (node (ref "C15") (pin "2") (pinfunction "2_2") (pintype "passive"))
      (node (ref "C16") (pin "2") (pinfunction "2_2") (pintype "passive"))
      (node (ref "C17") (pin "2") (pinfunction "2_2") (pintype "passive"))
      (node (ref "C18") (pin "2") (pinfunction "2_2") (pintype "passive"))
      (node (ref "C2") (pin "2") (pinfunction "2_2") (pintype "passive"))
      (node (ref "C20") (pin "2") (pinfunction "2_2") (pintype "passive"))
      (node (ref "C21") (pin "2") (pinfunction "2_2") (pintype "passive"))
      (node (ref "C24") (pin "2") (pinfunction "2_2") (pintype "passive"))
      (node (ref "C25") (pin "2") (pinfunction "2_2") (pintype "passive"))
      (node (ref "C26") (pin "2") (pinfunction "2_2") (pintype "passive"))
      (node (ref "C27") (pin "1") (pinfunction "1_1") (pintype "passive"))
      (node (ref "C28") (pin "1") (pinfunction "1_1") (pintype "passive"))
      (node (ref "C29") (pin "1") (pinfunction "1_1") (pintype "passive"))
      (node (ref "C3") (pin "2") (pinfunction "2_2") (pintype "passive"))
      (node (ref "C30") (pin "1") (pinfunction "1_1") (pintype "passive"))
      (node (ref "C31") (pin "1") (pinfunction "1_1") (pintype "passive"))
      (node (ref "C32") (pin "1") (pinfunction "1_1") (pintype "passive"))
      (node (ref "C33") (pin "2") (pinfunction "2_2") (pintype "passive"))
      (node (ref "C34") (pin "1") (pinfunction "1_1") (pintype "passive"))
      (node (ref "C4") (pin "2") (pinfunction "2_2") (pintype "passive"))
      (node (ref "C5") (pin "2") (pinfunction "2_2") (pintype "passive"))
      (node (ref "C6") (pin "2") (pinfunction "2_2") (pintype "passive"))
      (node (ref "C7") (pin "2") (pinfunction "2_2") (pintype "passive"))
      (node (ref "C8") (pin "2") (pinfunction "2_2") (pintype "passive"))
      (node (ref "C9") (pin "2") (pinfunction "2_2") (pintype "passive"))
      (node (ref "IC1") (pin "3") (pinfunction "GND_3") (pintype "passive"))
      (node (ref "IC2") (pin "8") (pinfunction "GND_8") (pintype "power_in"))
      (node (ref "IC3") (pin "14") (pinfunction "FI_14") (pintype "input"))
      (node (ref "IC3") (pin "8") (pinfunction "GND_8") (pintype "power_in"))
      (node (ref "IC4") (pin "11") (pinfunction "EI_11") (pintype "input"))
      (node (ref "IC4") (pin "14") (pinfunction "FI_14") (pintype "input"))
      (node (ref "IC4") (pin "5") (pinfunction "BI_5") (pintype "input"))
      (node (ref "IC4") (pin "7") (pinfunction "CI_7") (pintype "input"))
      (node (ref "IC4") (pin "8") (pinfunction "GND_8") (pintype "power_in"))
      (node (ref "IC4") (pin "9") (pinfunction "DI_9") (pintype "input"))
      (node (ref "IC5") (pin "3") (pinfunction "GND_3") (pintype "passive"))
      (node (ref "IC6") (pin "1") (pinfunction "-VIN_1") (pintype "bidirectional"))
      (node (ref "IC7") (pin "1") (pinfunction "G_1") (pintype "input"))
      (node (ref "IC7") (pin "10") (pinfunction "GND_10") (pintype "power_in"))
      (node (ref "IC7") (pin "17") (pinfunction "A4_17") (pintype "input"))
      (node (ref "IC7") (pin "19") (pinfunction "G_19") (pintype "input"))
      (node (ref "JP1") (pin "1") (pinfunction "1_1") (pintype "passive"))
      (node (ref "JP1") (pin "2") (pinfunction "2_2") (pintype "passive"))
      (node (ref "JP1") (pin "3") (pinfunction "3_3") (pintype "passive"))
      (node (ref "JP1") (pin "4") (pinfunction "4_4") (pintype "passive"))
      (node (ref "JP1") (pin "5") (pinfunction "5_5") (pintype "passive"))
      (node (ref "JP1") (pin "6") (pinfunction "6_6") (pintype "passive"))
      (node (ref "JP1") (pin "7") (pinfunction "7_7") (pintype "passive"))
      (node (ref "JP1") (pin "8") (pinfunction "8_8") (pintype "passive"))
      (node (ref "JP40") (pin "1") (pinfunction "1_1") (pintype "passive"))
      (node (ref "OK4") (pin "13") (pinfunction "EMIT_13") (pintype "passive"))
      (node (ref "OK4") (pin "15") (pinfunction "EMIT_15") (pintype "passive"))
      (node (ref "R7") (pin "2") (pinfunction "2_2") (pintype "passive"))
      (node (ref "SV1") (pin "18") (pinfunction "18_18") (pintype "passive"))
      (node (ref "SV1") (pin "20") (pinfunction "20_20") (pintype "passive"))
      (node (ref "SV2") (pin "20") (pinfunction "20_20") (pintype "passive"))
      (node (ref "U$15") (pin "10") (pinfunction "A-L_10") (pintype "passive"))
      (node (ref "U$15") (pin "12") (pinfunction "A-R_12") (pintype "passive"))
      (node (ref "U$15") (pin "8") (pinfunction "8_8") (pintype "input"))
      (node (ref "U2") (pin "11") (pinfunction "VSSRX_11") (pintype "power_in"))
      (node (ref "U2") (pin "18") (pinfunction "VSSTX_18") (pintype "power_in"))
      (node (ref "U2") (pin "2") (pinfunction "VSS_2") (pintype "power_in"))
      (node (ref "U2") (pin "21") (pinfunction "VSSPLL_21") (pintype "power_in"))
      (node (ref "U2") (pin "22") (pinfunction "VSSOSC_22") (pintype "power_in"))
      (node (ref "UEXT") (pin "2") (pinfunction "2_2") (pintype "passive"))
      (node (ref "X1") (pin "18") (pinfunction "18_18") (pintype "passive"))
      (node (ref "X1") (pin "19") (pinfunction "19_19") (pintype "passive"))
      (node (ref "X1") (pin "20") (pinfunction "20_20") (pintype "passive"))
      (node (ref "X1") (pin "21") (pinfunction "21_21") (pintype "passive"))
      (node (ref "X1") (pin "22") (pinfunction "22_22") (pintype "passive"))
      (node (ref "X1") (pin "23") (pinfunction "23_23") (pintype "passive"))
      (node (ref "X1") (pin "24") (pinfunction "24_24") (pintype "passive"))
      (node (ref "X1") (pin "25") (pinfunction "25_25") (pintype "passive"))
      (node (ref "X1") (pin "G1") (pinfunction "G1_G1") (pintype "passive"))
      (node (ref "X1") (pin "G2") (pinfunction "G2_G2") (pintype "passive"))
      (node (ref "X2") (pin "2") (pinfunction "1_2") (pintype "passive"))
      (node (ref "X3") (pin "2") (pinfunction "1_2") (pintype "passive"))
    )
    (net (code "17") (name "LIMIT_A") (class "Default")
      (node (ref "X1") (pin "16") (pinfunction "16_16") (pintype "passive"))
    )
    (net (code "18") (name "LIMIT_X") (class "Default")
      (node (ref "IC7") (pin "2") (pinfunction "A1_2") (pintype "input"))
      (node (ref "R14") (pin "2") (pinfunction "2_2") (pintype "passive"))
      (node (ref "X1") (pin "11") (pinfunction "11_11") (pintype "passive"))
    )
    (net (code "19") (name "LIMIT_Y") (class "Default")
      (node (ref "IC7") (pin "6") (pinfunction "A3_6") (pintype "input"))
      (node (ref "R3") (pin "2") (pinfunction "2_2") (pintype "passive"))
      (node (ref "X1") (pin "13") (pinfunction "13_13") (pintype "passive"))
    )
    (net (code "20") (name "LIMIT_Z") (class "Default")
      (node (ref "IC7") (pin "4") (pinfunction "A2_4") (pintype "input"))
      (node (ref "R2") (pin "2") (pinfunction "2_2") (pintype "passive"))
      (node (ref "X1") (pin "12") (pinfunction "12_12") (pintype "passive"))
    )
    (net (code "21") (name "MISO") (class "Default")
      (node (ref "U2") (pin "6") (pinfunction "SO_6") (pintype "output"))
      (node (ref "UEXT") (pin "7") (pinfunction "7_7") (pintype "passive"))
    )
    (net (code "22") (name "MOSI") (class "Default")
      (node (ref "U2") (pin "7") (pinfunction "SI_7") (pintype "input"))
      (node (ref "UEXT") (pin "8") (pinfunction "8_8") (pintype "passive"))
    )
    (net (code "23") (name "Net-(C7-Pad1)") (class "Default")
      (node (ref "C7") (pin "1") (pinfunction "1_1") (pintype "passive"))
      (node (ref "R76") (pin "2") (pinfunction "2_2") (pintype "passive"))
      (node (ref "R77") (pin "1") (pinfunction "1_1") (pintype "passive"))
    )
    (net (code "24") (name "Net-(C8-Pad1)") (class "Default")
      (node (ref "C8") (pin "1") (pinfunction "1_1") (pintype "passive"))
      (node (ref "JP39") (pin "1") (pinfunction "1_1") (pintype "passive"))
      (node (ref "R77") (pin "2") (pinfunction "2_2") (pintype "passive"))
      (node (ref "X3") (pin "1") (pinfunction "1_1") (pintype "passive"))
    )
    (net (code "25") (name "Net-(C33-Pad1)") (class "Default")
      (node (ref "C33") (pin "1") (pinfunction "1_1") (pintype "passive"))
      (node (ref "R79") (pin "2") (pinfunction "2_2") (pintype "passive"))
      (node (ref "R80") (pin "1") (pinfunction "1_1") (pintype "passive"))
      (node (ref "SJ1") (pin "1") (pinfunction "1_1") (pintype "passive"))
    )
    (net (code "26") (name "Net-(IC4A-AO)") (class "Default")
      (node (ref "IC4") (pin "2") (pinfunction "AO_2") (pintype "output"))
      (node (ref "R76") (pin "1") (pinfunction "1_1") (pintype "passive"))
    )
    (net (code "27") (name "Net-(IC6-+VOUT)") (class "Default")
      (node (ref "C19") (pin "1") (pinfunction "1_1") (pintype "passive"))
      (node (ref "C22") (pin "1") (pinfunction "1_1") (pintype "passive"))
      (node (ref "C23") (pin "1") (pinfunction "1_1") (pintype "passive"))
      (node (ref "IC6") (pin "4") (pinfunction "+VOUT_4") (pintype "bidirectional"))
      (node (ref "R1") (pin "1") (pinfunction "1_1") (pintype "passive"))
      (node (ref "R6") (pin "2") (pinfunction "2_2") (pintype "passive"))
      (node (ref "R8") (pin "1") (pinfunction "1_1") (pintype "passive"))
    )
    (net (code "28") (name "Net-(IC6--VOUT)") (class "Default")
      (node (ref "C19") (pin "2") (pinfunction "2_2") (pintype "passive"))
      (node (ref "C22") (pin "2") (pinfunction "2_2") (pintype "passive"))
      (node (ref "C23") (pin "2") (pinfunction "2_2") (pintype "passive"))
      (node (ref "IC6") (pin "3") (pinfunction "-VOUT_3") (pintype "bidirectional"))
      (node (ref "R6") (pin "1") (pinfunction "1_1") (pintype "passive"))
      (node (ref "X4") (pin "2") (pinfunction "1_2") (pintype "passive"))
    )
    (net (code "29") (name "Net-(L1-Pad1)") (class "Default")
      (node (ref "L1") (pin "1") (pinfunction "1_1") (pintype "passive"))
      (node (ref "X2") (pin "1") (pinfunction "1_1") (pintype "passive"))
    )
    (net (code "30") (name "Net-(OK4A-A)") (class "Default")
      (node (ref "OK4") (pin "1") (pinfunction "A_1") (pintype "passive"))
      (node (ref "R1") (pin "2") (pinfunction "2_2") (pintype "passive"))
    )
    (net (code "31") (name "Net-(OK4A-C)") (class "Default")
      (node (ref "OK4") (pin "2") (pinfunction "C_2") (pintype "passive"))
      (node (ref "X4") (pin "1") (pinfunction "1_1") (pintype "passive"))
    )
    (net (code "32") (name "Net-(OK4B-A)") (class "Default")
      (node (ref "OK4") (pin "3") (pinfunction "A_3") (pintype "passive"))
      (node (ref "R8") (pin "2") (pinfunction "2_2") (pintype "passive"))
    )
    (net (code "33") (name "Net-(OK4B-C)") (class "Default")
      (node (ref "JP3") (pin "1") (pinfunction "1_1") (pintype "passive"))
      (node (ref "OK4") (pin "4") (pinfunction "C_4") (pintype "passive"))
    )
    (net (code "34") (name "Net-(Q2-2)") (class "Default")
      (node (ref "C24") (pin "1") (pinfunction "1_1") (pintype "passive"))
      (node (ref "Q2") (pin "3") (pinfunction "2_3") (pintype "passive"))
      (node (ref "U2") (pin "24") (pinfunction "OSC2_24") (pintype "output"))
    )
    (net (code "35") (name "Net-(U$15-C-L)") (class "Default")
      (node (ref "R11") (pin "1") (pinfunction "1_1") (pintype "passive"))
      (node (ref "U$15") (pin "9") (pinfunction "C-L_9") (pintype "passive"))
    )
    (net (code "36") (name "Net-(U$15-C-R)") (class "Default")
      (node (ref "R10") (pin "1") (pinfunction "1_1") (pintype "passive"))
      (node (ref "U$15") (pin "11") (pinfunction "C-R_11") (pintype "passive"))
    )
    (net (code "37") (name "Net-(U$15-CR)") (class "Default")
      (node (ref "SJ1") (pin "2") (pinfunction "2_2") (pintype "passive"))
      (node (ref "U$15") (pin "5") (pinfunction "CR_5") (pintype "input"))
    )
    (net (code "38") (name "Net-(U$15-CT)") (class "Default")
      (node (ref "C34") (pin "2") (pinfunction "2_2") (pintype "passive"))
      (node (ref "L4") (pin "2") (pinfunction "2_2") (pintype "passive"))
      (node (ref "R81") (pin "2") (pinfunction "2_2") (pintype "passive"))
      (node (ref "R82") (pin "1") (pinfunction "1_1") (pintype "passive"))
      (node (ref "U$15") (pin "2") (pinfunction "CT_2") (pintype "input"))
    )
    (net (code "39") (name "Net-(U$15-RD+)") (class "Default")
      (node (ref "R80") (pin "2") (pinfunction "2_2") (pintype "passive"))
      (node (ref "U$15") (pin "4") (pinfunction "RD+_4") (pintype "input"))
      (node (ref "U2") (pin "13") (pinfunction "TPIN+_13") (pintype "input"))
    )
    (net (code "40") (name "Net-(U$15-RD-)") (class "Default")
      (node (ref "R79") (pin "1") (pinfunction "1_1") (pintype "passive"))
      (node (ref "U$15") (pin "6") (pinfunction "RD-_6") (pintype "input"))
      (node (ref "U2") (pin "12") (pinfunction "TPIN-_12") (pintype "input"))
    )
    (net (code "41") (name "Net-(U$15-TD+)") (class "Default")
      (node (ref "R82") (pin "2") (pinfunction "2_2") (pintype "passive"))
      (node (ref "U$15") (pin "1") (pinfunction "TD+_1") (pintype "input"))
      (node (ref "U2") (pin "17") (pinfunction "TPOUT+_17") (pintype "output"))
    )
    (net (code "42") (name "Net-(U$15-TD-)") (class "Default")
      (node (ref "R81") (pin "1") (pinfunction "1_1") (pintype "passive"))
      (node (ref "U$15") (pin "3") (pinfunction "TD-_3") (pintype "input"))
      (node (ref "U2") (pin "16") (pinfunction "TPOUT-_16") (pintype "output"))
    )
    (net (code "43") (name "Net-(U2-LEDA)") (class "Default")
      (node (ref "R10") (pin "2") (pinfunction "2_2") (pintype "passive"))
      (node (ref "U2") (pin "27") (pinfunction "LEDA_27") (pintype "output"))
    )
    (net (code "44") (name "Net-(U2-LEDB)") (class "Default")
      (node (ref "R11") (pin "2") (pinfunction "2_2") (pintype "passive"))
      (node (ref "U2") (pin "26") (pinfunction "LEDB_26") (pintype "output"))
    )
    (net (code "45") (name "Net-(U2-OSC1)") (class "Default")
      (node (ref "C26") (pin "1") (pinfunction "1_1") (pintype "passive"))
      (node (ref "Q2") (pin "1") (pinfunction "1_1") (pintype "passive"))
      (node (ref "U2") (pin "23") (pinfunction "OSC1_23") (pintype "input"))
    )
    (net (code "46") (name "Net-(U2-RBIAS)") (class "Default")
      (node (ref "R7") (pin "1") (pinfunction "1_1") (pintype "passive"))
      (node (ref "U2") (pin "14") (pinfunction "RBIAS_14") (pintype "passive"))
    )
    (net (code "47") (name "Net-(U2-VCAP)") (class "Default")
      (node (ref "C27") (pin "2") (pinfunction "2_2") (pintype "passive"))
      (node (ref "U2") (pin "1") (pinfunction "VCAP_1") (pintype "power_in"))
    )
    (net (code "48") (name "PROBE") (class "Default")
      (node (ref "IC7") (pin "8") (pinfunction "A4_8") (pintype "input"))
      (node (ref "R4") (pin "2") (pinfunction "2_2") (pintype "passive"))
      (node (ref "X1") (pin "15") (pinfunction "15_15") (pintype "passive"))
    )
    (net (code "49") (name "PROBE_ISOLATED") (class "Default")
      (node (ref "IC7") (pin "13") (pinfunction "A2_13") (pintype "input"))
      (node (ref "OK4") (pin "16") (pinfunction "COL_16") (pintype "passive"))
      (node (ref "R12") (pin "1") (pinfunction "1_1") (pintype "passive"))
    )
    (net (code "50") (name "RB0") (class "Default")
      (node (ref "IC7") (pin "16") (pinfunction "Y2_16") (pintype "tri_state"))
      (node (ref "SV2") (pin "16") (pinfunction "16_16") (pintype "passive"))
    )
    (net (code "51") (name "RB1") (class "Default")
      (node (ref "SV1") (pin "16") (pinfunction "16_16") (pintype "passive"))
    )
    (net (code "52") (name "RB2") (class "Default")
      (node (ref "SV1") (pin "15") (pinfunction "15_15") (pintype "passive"))
    )
    (net (code "53") (name "RB3") (class "Default")
      (node (ref "SV1") (pin "14") (pinfunction "14_14") (pintype "passive"))
    )
    (net (code "54") (name "RB4") (class "Default")
      (node (ref "SV1") (pin "13") (pinfunction "13_13") (pintype "passive"))
    )
    (net (code "55") (name "RB8") (class "Default")
      (node (ref "SV1") (pin "12") (pinfunction "12_12") (pintype "passive"))
    )
    (net (code "56") (name "RB9") (class "Default")
      (node (ref "SV1") (pin "11") (pinfunction "11_11") (pintype "passive"))
    )
    (net (code "57") (name "RB10") (class "Default")
      (node (ref "SV1") (pin "10") (pinfunction "10_10") (pintype "passive"))
    )
    (net (code "58") (name "RB11") (class "Default")
      (node (ref "SV1") (pin "9") (pinfunction "9_9") (pintype "passive"))
    )
    (net (code "59") (name "RB12") (class "Default")
      (node (ref "SV1") (pin "8") (pinfunction "8_8") (pintype "passive"))
    )
    (net (code "60") (name "RB17") (class "Default")
      (node (ref "SV1") (pin "7") (pinfunction "7_7") (pintype "passive"))
    )
    (net (code "61") (name "RC13") (class "Default")
      (node (ref "IC7") (pin "7") (pinfunction "Y2_7") (pintype "tri_state"))
      (node (ref "SV2") (pin "2") (pinfunction "2_2") (pintype "passive"))
    )
    (net (code "62") (name "RC14") (class "Default")
      (node (ref "IC7") (pin "5") (pinfunction "Y3_5") (pintype "tri_state"))
      (node (ref "SV2") (pin "1") (pinfunction "1_1") (pintype "passive"))
    )
    (net (code "63") (name "RD1") (class "Default")
      (node (ref "IC3") (pin "11") (pinfunction "EI_11") (pintype "input"))
      (node (ref "IC4") (pin "3") (pinfunction "AI_3") (pintype "input"))
      (node (ref "SV1") (pin "6") (pinfunction "6_6") (pintype "passive"))
    )
    (net (code "64") (name "RD2") (class "Default")
      (node (ref "SV1") (pin "5") (pinfunction "5_5") (pintype "passive"))
    )
    (net (code "65") (name "RD3") (class "Default")
      (node (ref "SV1") (pin "4") (pinfunction "4_4") (pintype "passive"))
    )
    (net (code "66") (name "RD4") (class "Default")
      (node (ref "IC3") (pin "9") (pinfunction "DI_9") (pintype "input"))
      (node (ref "SV1") (pin "3") (pinfunction "3_3") (pintype "passive"))
    )
    (net (code "67") (name "RD5") (class "Default")
      (node (ref "SV1") (pin "2") (pinfunction "2_2") (pintype "passive"))
    )
    (net (code "68") (name "RD6") (class "Default")
      (node (ref "SV1") (pin "1") (pinfunction "1_1") (pintype "passive"))
    )
    (net (code "69") (name "RD7") (class "Default")
      (node (ref "IC7") (pin "9") (pinfunction "Y1_9") (pintype "tri_state"))
      (node (ref "SV2") (pin "15") (pinfunction "15_15") (pintype "passive"))
    )
    (net (code "70") (name "RD8") (class "Default")
      (node (ref "IC7") (pin "12") (pinfunction "Y4_12") (pintype "tri_state"))
      (node (ref "SV2") (pin "14") (pinfunction "14_14") (pintype "passive"))
    )
    (net (code "71") (name "RD11") (class "Default")
      (node (ref "IC7") (pin "18") (pinfunction "Y1_18") (pintype "tri_state"))
      (node (ref "SV2") (pin "13") (pinfunction "13_13") (pintype "passive"))
    )
    (net (code "72") (name "RE0") (class "Default")
      (node (ref "IC2") (pin "3") (pinfunction "AI_3") (pintype "input"))
      (node (ref "SV2") (pin "3") (pinfunction "3_3") (pintype "passive"))
    )
    (net (code "73") (name "RE1") (class "Default")
      (node (ref "IC2") (pin "5") (pinfunction "BI_5") (pintype "input"))
      (node (ref "SV2") (pin "4") (pinfunction "4_4") (pintype "passive"))
    )
    (net (code "74") (name "RE2") (class "Default")
      (node (ref "IC2") (pin "7") (pinfunction "CI_7") (pintype "input"))
      (node (ref "SV2") (pin "5") (pinfunction "5_5") (pintype "passive"))
    )
    (net (code "75") (name "RE3") (class "Default")
      (node (ref "IC2") (pin "9") (pinfunction "DI_9") (pintype "input"))
      (node (ref "SV2") (pin "6") (pinfunction "6_6") (pintype "passive"))
    )
    (net (code "76") (name "RE4") (class "Default")
      (node (ref "IC2") (pin "11") (pinfunction "EI_11") (pintype "input"))
      (node (ref "SV2") (pin "7") (pinfunction "7_7") (pintype "passive"))
    )
    (net (code "77") (name "RE5") (class "Default")
      (node (ref "IC2") (pin "14") (pinfunction "FI_14") (pintype "input"))
      (node (ref "SV2") (pin "8") (pinfunction "8_8") (pintype "passive"))
    )
    (net (code "78") (name "RE6") (class "Default")
      (node (ref "IC3") (pin "3") (pinfunction "AI_3") (pintype "input"))
      (node (ref "SV2") (pin "9") (pinfunction "9_9") (pintype "passive"))
    )
    (net (code "79") (name "RE7") (class "Default")
      (node (ref "IC3") (pin "5") (pinfunction "BI_5") (pintype "input"))
      (node (ref "SV2") (pin "10") (pinfunction "10_10") (pintype "passive"))
    )
    (net (code "80") (name "RF1") (class "Default")
      (node (ref "IC3") (pin "7") (pinfunction "CI_7") (pintype "input"))
      (node (ref "SV2") (pin "11") (pinfunction "11_11") (pintype "passive"))
    )
    (net (code "81") (name "RG9") (class "Default")
      (node (ref "IC7") (pin "14") (pinfunction "Y3_14") (pintype "tri_state"))
      (node (ref "SV2") (pin "12") (pinfunction "12_12") (pintype "passive"))
    )
    (net (code "82") (name "RXD") (class "Default")
      (node (ref "UEXT") (pin "4") (pinfunction "4_4") (pintype "passive"))
    )
    (net (code "83") (name "SCK{slash}LED1") (class "Default")
      (node (ref "U2") (pin "8") (pinfunction "SCK_8") (pintype "input"))
      (node (ref "UEXT") (pin "9") (pinfunction "9_9") (pintype "passive"))
    )
    (net (code "84") (name "SCL") (class "Default")
      (node (ref "UEXT") (pin "5") (pinfunction "5_5") (pintype "passive"))
    )
    (net (code "85") (name "SDA") (class "Default")
      (node (ref "UEXT") (pin "6") (pinfunction "6_6") (pintype "passive"))
    )
    (net (code "86") (name "SPINDLE_ENABLE") (class "Default")
      (node (ref "IC3") (pin "10") (pinfunction "DO_10") (pintype "output"))
      (node (ref "X1") (pin "17") (pinfunction "17_17") (pintype "passive"))
    )
    (net (code "87") (name "SPINDLE_PWM") (class "Default")
      (node (ref "IC3") (pin "12") (pinfunction "EO_12") (pintype "output"))
      (node (ref "X1") (pin "1") (pinfunction "1_1") (pintype "passive"))
    )
    (net (code "88") (name "STEPPER_ENABLE") (class "Default")
      (node (ref "IC3") (pin "2") (pinfunction "AO_2") (pintype "output"))
      (node (ref "X1") (pin "14") (pinfunction "14_14") (pintype "passive"))
    )
    (net (code "89") (name "STEP_A") (class "Default")
      (node (ref "IC3") (pin "4") (pinfunction "BO_4") (pintype "output"))
      (node (ref "X1") (pin "8") (pinfunction "8_8") (pintype "passive"))
    )
    (net (code "90") (name "STEP_X") (class "Default")
      (node (ref "IC2") (pin "2") (pinfunction "AO_2") (pintype "output"))
      (node (ref "X1") (pin "2") (pinfunction "2_2") (pintype "passive"))
    )
    (net (code "91") (name "STEP_Y") (class "Default")
      (node (ref "IC2") (pin "6") (pinfunction "CO_6") (pintype "output"))
      (node (ref "X1") (pin "4") (pinfunction "4_4") (pintype "passive"))
    )
    (net (code "92") (name "STEP_Z") (class "Default")
      (node (ref "IC2") (pin "12") (pinfunction "EO_12") (pintype "output"))
      (node (ref "X1") (pin "6") (pinfunction "6_6") (pintype "passive"))
    )
    (net (code "93") (name "TXD") (class "Default")
      (node (ref "UEXT") (pin "3") (pinfunction "3_3") (pintype "passive"))
    )
    (net (code "94") (name "UEXT_#CS") (class "Default")
      (node (ref "R124") (pin "2") (pinfunction "2_2") (pintype "passive"))
      (node (ref "U2") (pin "9") (pinfunction "CS_9") (pintype "input"))
      (node (ref "UEXT") (pin "10") (pinfunction "10_10") (pintype "passive"))
    )
    (net (code "95") (name "unconnected-(IC3A-FO-Pad15)") (class "Default")
      (node (ref "IC3") (pin "15") (pinfunction "FO_15") (pintype "output"))
    )
    (net (code "96") (name "unconnected-(IC4A-BO-Pad4)") (class "Default")
      (node (ref "IC4") (pin "4") (pinfunction "BO_4") (pintype "output"))
    )
    (net (code "97") (name "unconnected-(IC4A-CO-Pad6)") (class "Default")
      (node (ref "IC4") (pin "6") (pinfunction "CO_6") (pintype "output"))
    )
    (net (code "98") (name "unconnected-(IC4A-DO-Pad10)") (class "Default")
      (node (ref "IC4") (pin "10") (pinfunction "DO_10") (pintype "output"))
    )
    (net (code "99") (name "unconnected-(IC4A-EO-Pad12)") (class "Default")
      (node (ref "IC4") (pin "12") (pinfunction "EO_12") (pintype "output"))
    )
    (net (code "100") (name "unconnected-(IC4A-FO-Pad15)") (class "Default")
      (node (ref "IC4") (pin "15") (pinfunction "FO_15") (pintype "output"))
    )
    (net (code "101") (name "unconnected-(IC7B-Y4-Pad3)") (class "Default")
      (node (ref "IC7") (pin "3") (pinfunction "Y4_3") (pintype "tri_state"))
    )
    (net (code "102") (name "unconnected-(U2-CLKOUT-Pad3)") (class "Default")
      (node (ref "U2") (pin "3") (pinfunction "CLKOUT_3") (pintype "output"))
    )
    (net (code "103") (name "unconnected-(UEXT-Pad1)") (class "Default")
      (node (ref "UEXT") (pin "1") (pinfunction "1_1") (pintype "passive"))
    )
    (net (code "104") (name "~{PROBE_ISOLATED}") (class "Default")
      (node (ref "IC7") (pin "15") (pinfunction "A3_15") (pintype "input"))
      (node (ref "OK4") (pin "14") (pinfunction "COL_14") (pintype "passive"))
      (node (ref "R13") (pin "1") (pinfunction "1_1") (pintype "passive"))
    )
  )
)
